# Adquisicion_de_se_al_y_preamplificacion.net
KiCad netlist of a schematic drawn in Altium Designer
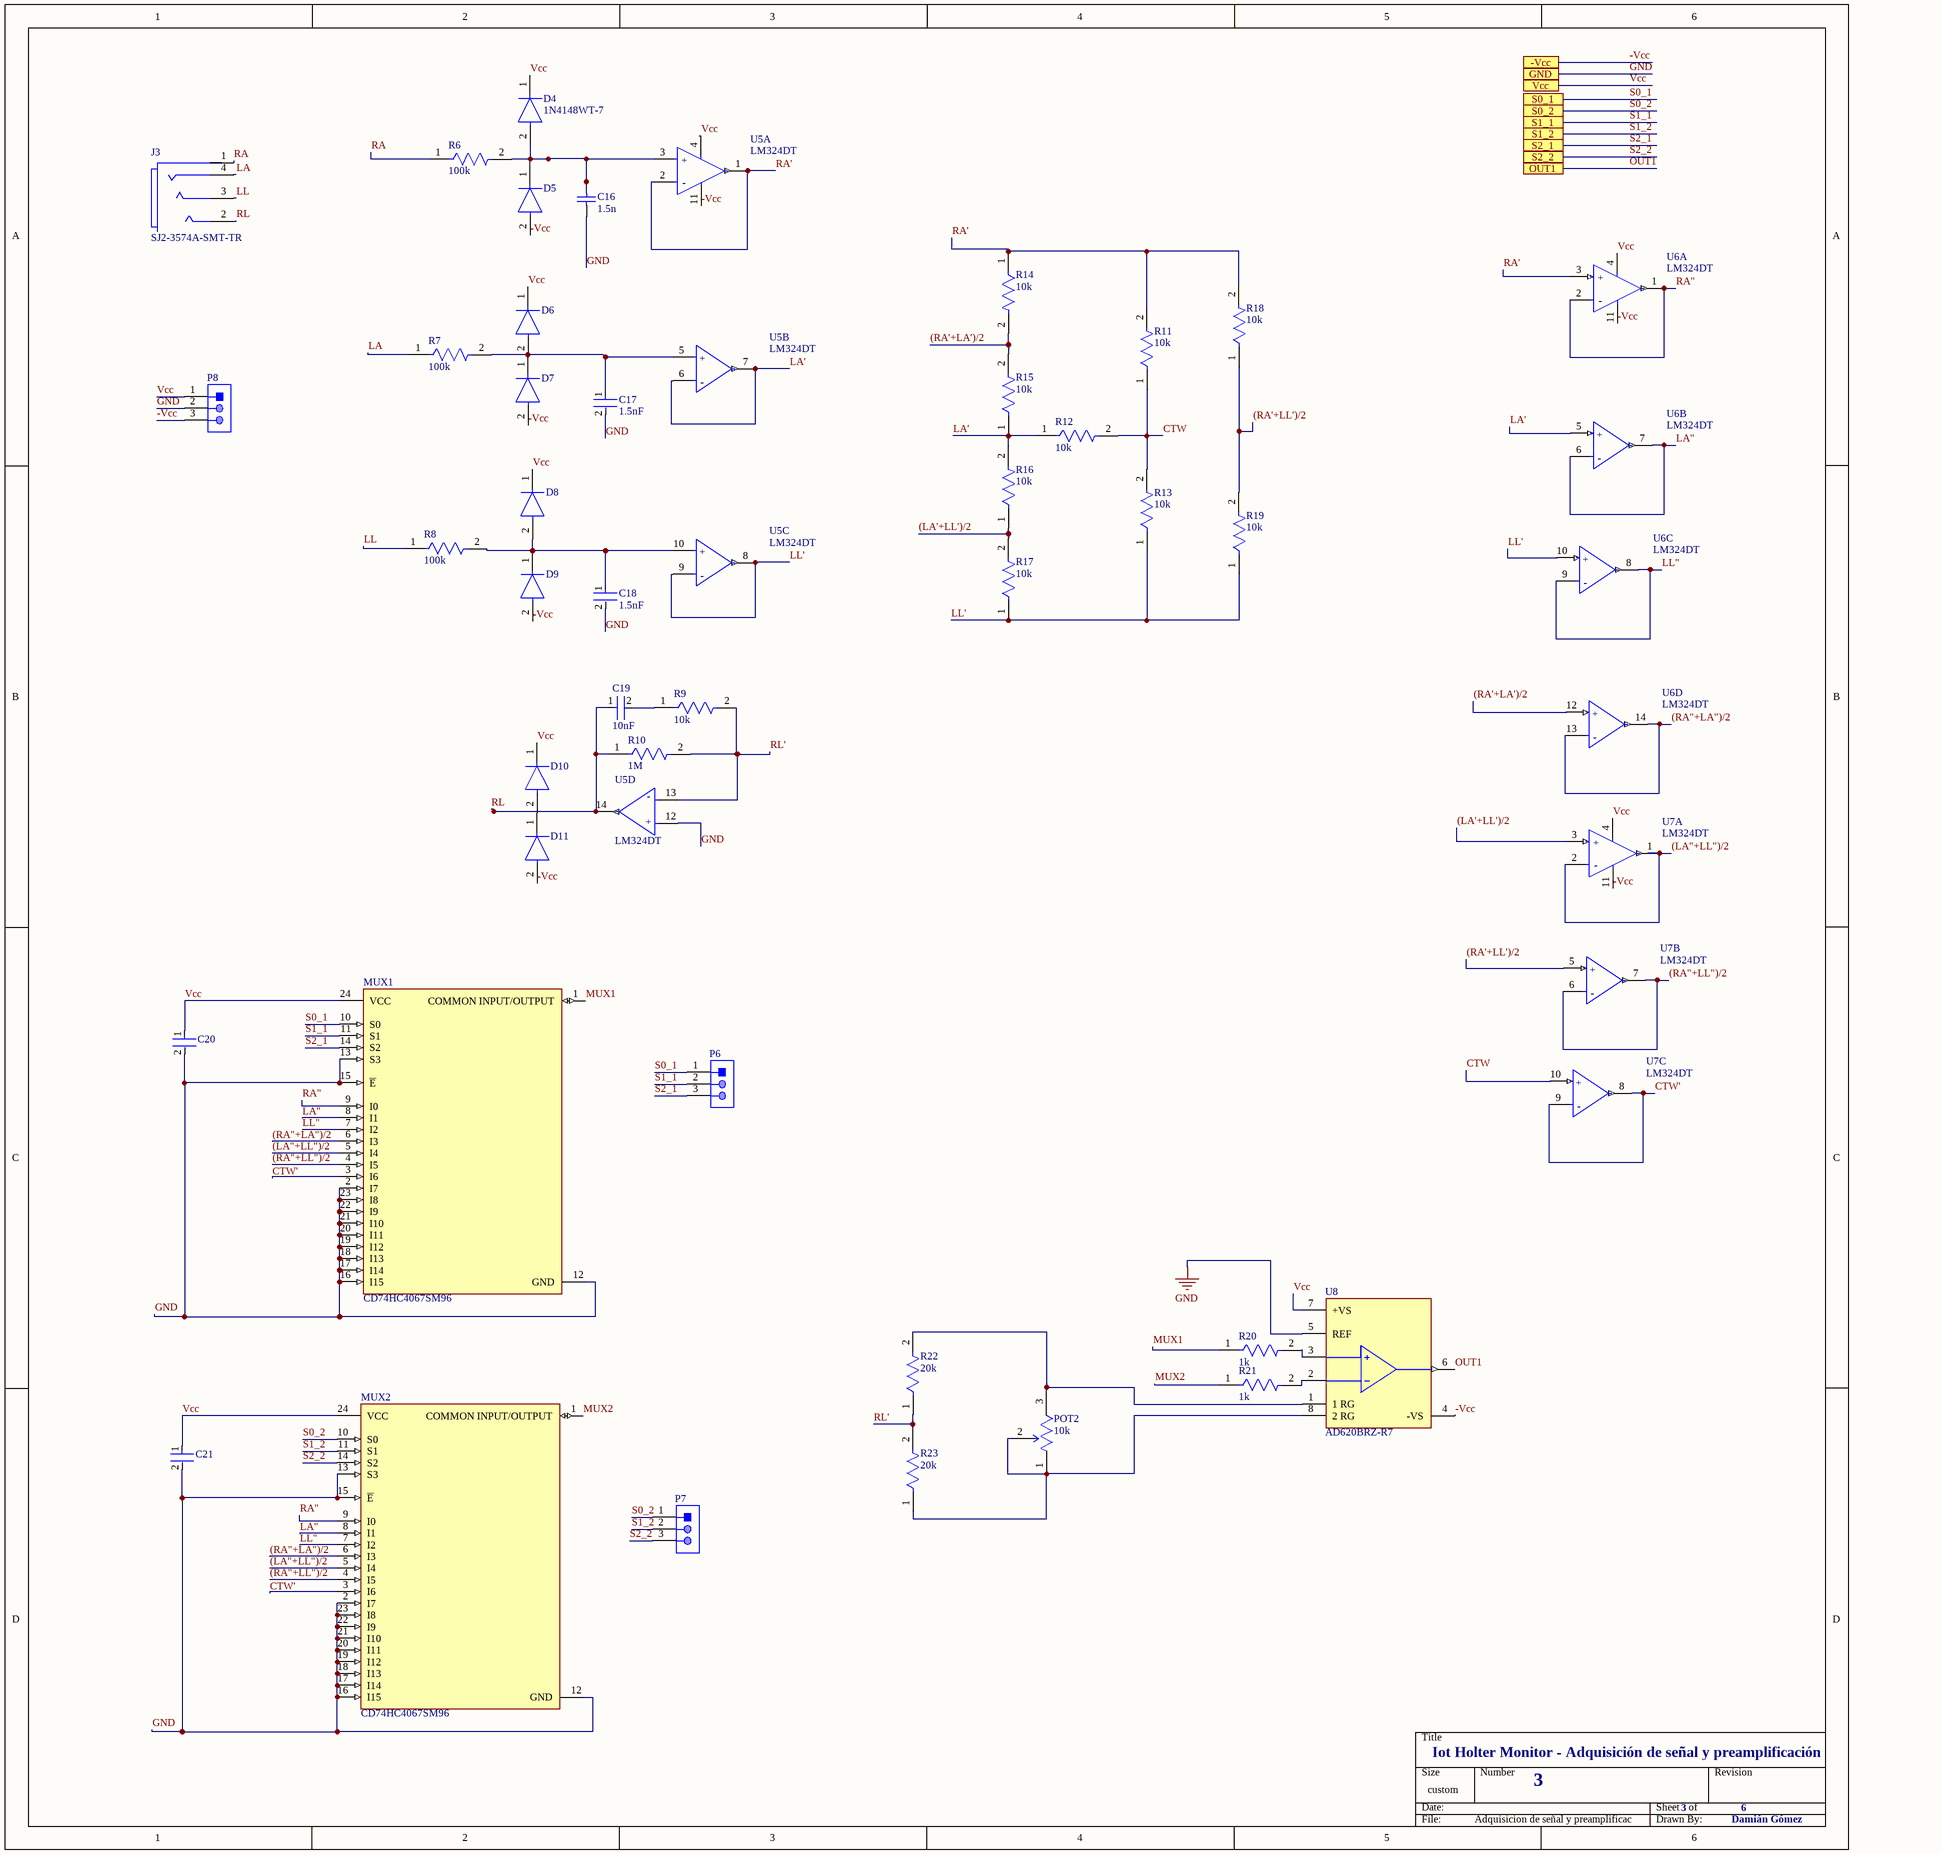
[diagram p0: Adquisicion de señal y preamplificacion.SchDoc]

(export (version "E")
  (design (tool "Eeschema 10.0.6"))
  (components
    (comp (ref "C16")
      (value "1.5n")
      (footprint "KEMT-1206-2_M")
      (description "CAP, Ceramic, 0.1 uF, +/- 10%, 50 V, -55 to 125 degC, 1206 (3216 Metric), RoHS, Tape and Reel")
      (fields (field (name "MANUFACTURER") "Kemet"))
      (libsource (lib "Altium Content Vault") (part "CAP-NP-2"))
    )
    (comp (ref "C17")
      (value "1.5nF")
      (footprint "FP-CL31-IPC_C")
      (description "Cap Ceramic 1.5nF 500V C0G ±5% SMD 1206 +125°C Embossed T/R")
      (fields (field (name "TOLERANCE") "5%"))
      (libsource (lib "Altium Content Vault") (part "b4654b650e69147ec39a6b967a45e02"))
    )
    (comp (ref "C18")
      (value "1.5nF")
      (footprint "FP-CL31-IPC_C")
      (description "Cap Ceramic 1.5nF 500V C0G ±5% SMD 1206 +125°C Embossed T/R")
      (fields (field (name "TOLERANCE") "5%"))
      (libsource (lib "Altium Content Vault") (part "b4654b650e69147ec39a6b967a45e02"))
    )
    (comp (ref "C19")
      (value "10nF")
      (footprint "FP-CL31-IPC_C")
      (description "Cap Ceramic 10nF 500V C0G ±5% SMD 1206 +125°C Embossed T/R")
      (fields (field (name "TOLERANCE") "5%"))
      (libsource (lib "Altium Content Vault") (part "b4654b650e69147ec39a6b967a45e02"))
    )
    (comp (ref "C20")
      (value "~")
      (footprint "FP-0603-L_1_6_0_15-W_0_81-IPC_A")
      (description "General Purpose Ceramic Capacitor, 0603, 1nF, 10%, X7R, 15%, 50V")
      (fields (field (name "VOLTAGE") "50V") (field (name "TOLERANCE") "10%"))
      (libsource (lib "Altium Content Vault") (part "02cd4be3c70576c341d710602a673aa"))
    )
    (comp (ref "C21")
      (value "~")
      (footprint "FP-0603-L_1_6_0_15-W_0_81-IPC_A")
      (description "General Purpose Ceramic Capacitor, 0603, 1nF, 10%, X7R, 15%, 50V")
      (fields (field (name "VOLTAGE") "50V") (field (name "TOLERANCE") "10%"))
      (libsource (lib "Altium Content Vault") (part "02cd4be3c70576c341d710602a673aa"))
    )
    (comp (ref "D4")
      (value "1N4148WT-7")
      (footprint "FP-SOD523-MFG")
      (description "DIODE GEN PURP 80V 125MA SOD523")
      (libsource (lib "Altium Content Vault") (part "d7152d700b627762746794eb795d46e"))
    )
    (comp (ref "D5")
      (value "1N4148WT-7")
      (footprint "FP-SOD523-MFG")
      (description "DIODE GEN PURP 80V 125MA SOD523")
      (libsource (lib "Altium Content Vault") (part "d7152d700b627762746794eb795d46e"))
    )
    (comp (ref "D6")
      (value "1N4148WT-7")
      (footprint "FP-SOD523-MFG")
      (description "DIODE GEN PURP 80V 125MA SOD523")
      (libsource (lib "Altium Content Vault") (part "d7152d700b627762746794eb795d46e"))
    )
    (comp (ref "D7")
      (value "1N4148WT-7")
      (footprint "FP-SOD523-MFG")
      (description "DIODE GEN PURP 80V 125MA SOD523")
      (libsource (lib "Altium Content Vault") (part "d7152d700b627762746794eb795d46e"))
    )
    (comp (ref "D8")
      (value "1N4148WT-7")
      (footprint "FP-SOD523-MFG")
      (description "DIODE GEN PURP 80V 125MA SOD523")
      (libsource (lib "Altium Content Vault") (part "d7152d700b627762746794eb795d46e"))
    )
    (comp (ref "D9")
      (value "1N4148WT-7")
      (footprint "FP-SOD523-MFG")
      (description "DIODE GEN PURP 80V 125MA SOD523")
      (libsource (lib "Altium Content Vault") (part "d7152d700b627762746794eb795d46e"))
    )
    (comp (ref "D10")
      (value "1N4148WT-7")
      (footprint "FP-SOD523-MFG")
      (description "DIODE GEN PURP 80V 125MA SOD523")
      (libsource (lib "Altium Content Vault") (part "d7152d700b627762746794eb795d46e"))
    )
    (comp (ref "D11")
      (value "1N4148WT-7")
      (footprint "FP-SOD523-MFG")
      (description "DIODE GEN PURP 80V 125MA SOD523")
      (libsource (lib "Altium Content Vault") (part "d7152d700b627762746794eb795d46e"))
    )
    (comp (ref "J3")
      (value "SJ2-3574A-SMT-TR")
      (footprint "FP-SJ2-3574A-SMT-TR-MFG")
      (description "AUDIO JACK, 3.5 MM, RT, 4 CONDUC")
      (fields
        (field (name "MANUFACTURER") "CUI")
        (field (name "OCTOPART") "https://octopart.com/sj2-3574a-smt-tr-cui-77838840")
      )
      (libsource (lib "Altium Content Vault") (part "faef30e0bf83b6fb70fb5141942b187"))
    )
    (comp (ref "MUX1")
      (value "CD74HC4067SM96")
      (footprint "FP-DB0024A-IPC_C")
      (description "IC MUX/DEMUX 1X16 24SSOP")
      (libsource (lib "Altium Content Vault") (part "3c03c7c8a240a5fb11098c607706683"))
    )
    (comp (ref "MUX2")
      (value "CD74HC4067SM96")
      (footprint "FP-DB0024A-IPC_C")
      (description "IC MUX/DEMUX 1X16 24SSOP")
      (libsource (lib "Altium Content Vault") (part "3c03c7c8a240a5fb11098c607706683"))
    )
    (comp (ref "P6")
      (value "640456-3")
      (footprint "TECO-640456-3")
      (description "Male Header, Pitch 2.54 mm, 1 x 3 Position, Height 10.03 mm, Tail Length 3.56 mm, -55 to 105 degC")
      (fields (field (name "MANUFACTURER") "TE Connectivity"))
      (libsource (lib "Altium Content Vault") (part "CN-1P-M-R3"))
    )
    (comp (ref "P7")
      (value "640456-3")
      (footprint "TECO-640456-3")
      (description "Male Header, Pitch 2.54 mm, 1 x 3 Position, Height 10.03 mm, Tail Length 3.56 mm, -55 to 105 degC")
      (fields (field (name "MANUFACTURER") "TE Connectivity"))
      (libsource (lib "Altium Content Vault") (part "CN-1P-M-R3"))
    )
    (comp (ref "P8")
      (value "640456-3")
      (footprint "TECO-640456-3")
      (description "Male Header, Pitch 2.54 mm, 1 x 3 Position, Height 10.03 mm, Tail Length 3.56 mm, -55 to 105 degC")
      (fields (field (name "MANUFACTURER") "TE Connectivity"))
      (libsource (lib "Altium Content Vault") (part "CN-1P-M-R3"))
    )
    (comp (ref "POT2")
      (value "10k")
      (footprint "FP-3296W-MFG")
      (description "TRIMMER 10K OHM 0.5W PC PIN TOP")
      (fields (field (name "TOLERANCE") "10%"))
      (libsource (lib "Altium Content Vault") (part "194907ebf2981c0cdd5d9631a0af656"))
    )
    (comp (ref "R6")
      (value "100k")
      (footprint "FP-RC3216-MFG")
      (description "Res Thick Film 1206 1kΩ 5% 0.25W ±100ppm/°C Molded SMD T/R")
      (fields (field (name "TOLERANCE") "5%"))
      (libsource (lib "Altium Content Vault") (part "1029c3af85768c4190bb7ad29bc67b5"))
    )
    (comp (ref "R7")
      (value "100k")
      (footprint "FP-RC3216-MFG")
      (description "Res Thick Film 1206 1kΩ 5% 0.25W ±100ppm/°C Molded SMD T/R")
      (fields (field (name "TOLERANCE") "5%"))
      (libsource (lib "Altium Content Vault") (part "1029c3af85768c4190bb7ad29bc67b5"))
    )
    (comp (ref "R8")
      (value "100k")
      (footprint "FP-RC3216-MFG")
      (description "Res Thick Film 1206 1kΩ 5% 0.25W ±100ppm/°C Molded SMD T/R")
      (fields (field (name "TOLERANCE") "5%"))
      (libsource (lib "Altium Content Vault") (part "1029c3af85768c4190bb7ad29bc67b5"))
    )
    (comp (ref "R9")
      (value "10k")
      (footprint "FP-RC3216-MFG")
      (description "Res Thick Film 1206 10kΩ 5% 0.25W ±100ppm/°C Molded SMD T/R")
      (fields (field (name "TOLERANCE") "5%"))
      (libsource (lib "Altium Content Vault") (part "1029c3af85768c4190bb7ad29bc67b5"))
    )
    (comp (ref "R10")
      (value "1M")
      (footprint "FP-RC3216-MFG")
      (description "Res Thick Film 1206 1MΩ 5% 0.25W ±100ppm/°C Molded SMD T/R")
      (fields (field (name "TOLERANCE") "5%"))
      (libsource (lib "Altium Content Vault") (part "1029c3af85768c4190bb7ad29bc67b5"))
    )
    (comp (ref "R11")
      (value "10k")
      (footprint "FP-RC3216-MFG")
      (description "Res Thick Film 1206 10kΩ 5% 0.25W ±100ppm/°C Molded SMD T/R")
      (fields (field (name "TOLERANCE") "5%"))
      (libsource (lib "Altium Content Vault") (part "1029c3af85768c4190bb7ad29bc67b5"))
    )
    (comp (ref "R12")
      (value "10k")
      (footprint "FP-RC3216-MFG")
      (description "Res Thick Film 1206 10kΩ 5% 0.25W ±100ppm/°C Molded SMD T/R")
      (fields (field (name "TOLERANCE") "5%"))
      (libsource (lib "Altium Content Vault") (part "1029c3af85768c4190bb7ad29bc67b5"))
    )
    (comp (ref "R13")
      (value "10k")
      (footprint "FP-RC3216-MFG")
      (description "Res Thick Film 1206 10kΩ 5% 0.25W ±100ppm/°C Molded SMD T/R")
      (fields (field (name "TOLERANCE") "5%"))
      (libsource (lib "Altium Content Vault") (part "1029c3af85768c4190bb7ad29bc67b5"))
    )
    (comp (ref "R14")
      (value "10k")
      (footprint "FP-RC3216-MFG")
      (description "Res Thick Film 1206 10kΩ 5% 0.25W ±100ppm/°C Molded SMD T/R")
      (fields (field (name "TOLERANCE") "5%"))
      (libsource (lib "Altium Content Vault") (part "1029c3af85768c4190bb7ad29bc67b5"))
    )
    (comp (ref "R15")
      (value "10k")
      (footprint "FP-RC3216-MFG")
      (description "Res Thick Film 1206 10kΩ 5% 0.25W ±100ppm/°C Molded SMD T/R")
      (fields (field (name "TOLERANCE") "5%"))
      (libsource (lib "Altium Content Vault") (part "1029c3af85768c4190bb7ad29bc67b5"))
    )
    (comp (ref "R16")
      (value "10k")
      (footprint "FP-RC3216-MFG")
      (description "Res Thick Film 1206 10kΩ 5% 0.25W ±100ppm/°C Molded SMD T/R")
      (fields (field (name "TOLERANCE") "5%"))
      (libsource (lib "Altium Content Vault") (part "1029c3af85768c4190bb7ad29bc67b5"))
    )
    (comp (ref "R17")
      (value "10k")
      (footprint "FP-RC3216-MFG")
      (description "Res Thick Film 1206 10kΩ 5% 0.25W ±100ppm/°C Molded SMD T/R")
      (fields (field (name "TOLERANCE") "5%"))
      (libsource (lib "Altium Content Vault") (part "1029c3af85768c4190bb7ad29bc67b5"))
    )
    (comp (ref "R18")
      (value "10k")
      (footprint "FP-RC3216-MFG")
      (description "Res Thick Film 1206 10kΩ 5% 0.25W ±100ppm/°C Molded SMD T/R")
      (fields (field (name "TOLERANCE") "5%"))
      (libsource (lib "Altium Content Vault") (part "1029c3af85768c4190bb7ad29bc67b5"))
    )
    (comp (ref "R19")
      (value "10k")
      (footprint "FP-RC3216-MFG")
      (description "Res Thick Film 1206 10kΩ 5% 0.25W ±100ppm/°C Molded SMD T/R")
      (fields (field (name "TOLERANCE") "5%"))
      (libsource (lib "Altium Content Vault") (part "1029c3af85768c4190bb7ad29bc67b5"))
    )
    (comp (ref "R20")
      (value "1k")
      (footprint "FP-RC3216-MFG")
      (description "Res Thick Film 1206 1kΩ 5% 0.25W ±100ppm/°C Molded SMD T/R")
      (fields (field (name "TOLERANCE") "5%"))
      (libsource (lib "Altium Content Vault") (part "1029c3af85768c4190bb7ad29bc67b5"))
    )
    (comp (ref "R21")
      (value "1k")
      (footprint "FP-RC3216-MFG")
      (description "Res Thick Film 1206 1kΩ 5% 0.25W ±100ppm/°C Molded SMD T/R")
      (fields (field (name "TOLERANCE") "5%"))
      (libsource (lib "Altium Content Vault") (part "1029c3af85768c4190bb7ad29bc67b5"))
    )
    (comp (ref "R22")
      (value "20k")
      (footprint "FP-RC3216-MFG")
      (description "Res Thick Film 1206 20kΩ 5% 0.25W ±100ppm/°C Molded SMD T/R")
      (fields (field (name "TOLERANCE") "5%"))
      (libsource (lib "Altium Content Vault") (part "1029c3af85768c4190bb7ad29bc67b5"))
    )
    (comp (ref "R23")
      (value "20k")
      (footprint "FP-RC3216-MFG")
      (description "Res Thick Film 1206 20kΩ 5% 0.25W ±100ppm/°C Molded SMD T/R")
      (fields (field (name "TOLERANCE") "5%"))
      (libsource (lib "Altium Content Vault") (part "1029c3af85768c4190bb7ad29bc67b5"))
    )
    (comp (ref "U5")
      (value "LM324DT")
      (footprint "FP-SO-14-MFG")
      (description "IC OPAMP GP 4 CIRCUIT 14SO")
      (fields
        (field (name "OCTOPART") "https://octopart.com/lm324dt-stmicroelectronics-39579146")
        (field (name "MANUFACTURER") "STMicroelectronics")
      )
      (libsource (lib "Altium Content Vault") (part "a065ef67e5aa9ef3942d43d6008d043"))
    )
    (comp (ref "U6")
      (value "LM324DT")
      (footprint "FP-SO-14-MFG")
      (description "IC OPAMP GP 4 CIRCUIT 14SO")
      (fields
        (field (name "OCTOPART") "https://octopart.com/lm324dt-stmicroelectronics-39579146")
        (field (name "MANUFACTURER") "STMicroelectronics")
      )
      (libsource (lib "Altium Content Vault") (part "a065ef67e5aa9ef3942d43d6008d043"))
    )
    (comp (ref "U7")
      (value "LM324DT")
      (footprint "FP-SO-14-MFG")
      (description "IC OPAMP GP 4 CIRCUIT 14SO")
      (fields
        (field (name "OCTOPART") "https://octopart.com/lm324dt-stmicroelectronics-39579146")
        (field (name "MANUFACTURER") "STMicroelectronics")
      )
      (libsource (lib "Altium Content Vault") (part "a065ef67e5aa9ef3942d43d6008d043"))
    )
    (comp (ref "U8")
      (value "AD620BRZ-R7")
      (footprint "FP-R-8-IPC_C")
      (description "IC INST AMP 1 CIRCUIT 8SOIC")
      (libsource (lib "Altium Content Vault") (part "34122d4f8c853147fd0c9ba0f33876e"))
    )
  )
  (nets
    (net (code "1") (name "/(LA\"+LL\"){slash}2") (class "Default")
      (node (ref "MUX1") (pin "5") (pinfunction "I4_5") (pintype "input"))
      (node (ref "MUX2") (pin "5") (pinfunction "I4_5") (pintype "input"))
      (node (ref "U7") (pin "1") (pinfunction "Output_1_1") (pintype "output"))
      (node (ref "U7") (pin "2") (pinfunction "Inverting_Input_1_2") (pintype "passive"))
    )
    (net (code "2") (name "/(LA'+LL'){slash}2") (class "Default")
      (node (ref "R16") (pin "1") (pinfunction "1_1") (pintype "passive"))
      (node (ref "R17") (pin "2") (pinfunction "2_2") (pintype "passive"))
      (node (ref "U7") (pin "3") (pinfunction "Non-Inverting_Input_1_3") (pintype "tri_state"))
    )
    (net (code "3") (name "/(RA\"+LA\"){slash}2") (class "Default")
      (node (ref "MUX1") (pin "6") (pinfunction "I3_6") (pintype "input"))
      (node (ref "MUX2") (pin "6") (pinfunction "I3_6") (pintype "input"))
      (node (ref "U6") (pin "13") (pinfunction "Inverting_Input_4_13") (pintype "tri_state"))
      (node (ref "U6") (pin "14") (pinfunction "Output_4_14") (pintype "output"))
    )
    (net (code "4") (name "/(RA\"+LL\"){slash}2") (class "Default")
      (node (ref "MUX1") (pin "4") (pinfunction "I5_4") (pintype "input"))
      (node (ref "MUX2") (pin "4") (pinfunction "I5_4") (pintype "input"))
      (node (ref "U7") (pin "6") (pinfunction "Inverting_Input_2_6") (pintype "tri_state"))
      (node (ref "U7") (pin "7") (pinfunction "Output_2_7") (pintype "output"))
    )
    (net (code "5") (name "/(RA'+LA'){slash}2") (class "Default")
      (node (ref "R14") (pin "2") (pinfunction "2_2") (pintype "passive"))
      (node (ref "R15") (pin "2") (pinfunction "2_2") (pintype "passive"))
      (node (ref "U6") (pin "12") (pinfunction "Non-Inverting_Input_4_12") (pintype "tri_state"))
    )
    (net (code "6") (name "/(RA'+LL'){slash}2") (class "Default")
      (node (ref "R18") (pin "1") (pinfunction "1_1") (pintype "passive"))
      (node (ref "R19") (pin "2") (pinfunction "2_2") (pintype "passive"))
      (node (ref "U7") (pin "5") (pinfunction "Non-Inverting_Input_2_5") (pintype "tri_state"))
    )
    (net (code "7") (name "/-Vcc") (class "Default")
      (node (ref "D11") (pin "2") (pinfunction "A_2") (pintype "passive"))
      (node (ref "D5") (pin "2") (pinfunction "A_2") (pintype "passive"))
      (node (ref "D7") (pin "2") (pinfunction "A_2") (pintype "passive"))
      (node (ref "D9") (pin "2") (pinfunction "A_2") (pintype "passive"))
      (node (ref "P8") (pin "3") (pinfunction "3_3") (pintype "passive"))
      (node (ref "U5") (pin "11") (pinfunction "VCC-_11") (pintype "power_in"))
      (node (ref "U6") (pin "11") (pinfunction "VCC-_11") (pintype "power_in"))
      (node (ref "U7") (pin "11") (pinfunction "VCC-_11") (pintype "power_in"))
      (node (ref "U8") (pin "4") (pinfunction "-VS_4") (pintype "power_in"))
    )
    (net (code "8") (name "/CTW") (class "Default")
      (node (ref "R11") (pin "1") (pinfunction "1_1") (pintype "passive"))
      (node (ref "R12") (pin "2") (pinfunction "2_2") (pintype "passive"))
      (node (ref "R13") (pin "2") (pinfunction "2_2") (pintype "passive"))
      (node (ref "U7") (pin "10") (pinfunction "Non-Inverting_Input_3_10") (pintype "tri_state"))
    )
    (net (code "9") (name "/CTW'") (class "Default")
      (node (ref "MUX1") (pin "3") (pinfunction "I6_3") (pintype "input"))
      (node (ref "MUX2") (pin "3") (pinfunction "I6_3") (pintype "input"))
      (node (ref "U7") (pin "8") (pinfunction "Output_3_8") (pintype "output"))
      (node (ref "U7") (pin "9") (pinfunction "Inverting_Input_3_9") (pintype "tri_state"))
    )
    (net (code "10") (name "/LA") (class "Default")
      (node (ref "J3") (pin "4") (pinfunction "ring_2_4") (pintype "passive"))
      (node (ref "R7") (pin "1") (pinfunction "1_1") (pintype "passive"))
    )
    (net (code "11") (name "/LA\"") (class "Default")
      (node (ref "MUX1") (pin "8") (pinfunction "I1_8") (pintype "input"))
      (node (ref "MUX2") (pin "8") (pinfunction "I1_8") (pintype "input"))
      (node (ref "U6") (pin "6") (pinfunction "Inverting_Input_2_6") (pintype "tri_state"))
      (node (ref "U6") (pin "7") (pinfunction "Output_2_7") (pintype "output"))
    )
    (net (code "12") (name "/LA'") (class "Default")
      (node (ref "R12") (pin "1") (pinfunction "1_1") (pintype "passive"))
      (node (ref "R15") (pin "1") (pinfunction "1_1") (pintype "passive"))
      (node (ref "R16") (pin "2") (pinfunction "2_2") (pintype "passive"))
      (node (ref "U5") (pin "6") (pinfunction "Inverting_Input_2_6") (pintype "tri_state"))
      (node (ref "U5") (pin "7") (pinfunction "Output_2_7") (pintype "output"))
      (node (ref "U6") (pin "5") (pinfunction "Non-Inverting_Input_2_5") (pintype "tri_state"))
    )
    (net (code "13") (name "/LL") (class "Default")
      (node (ref "J3") (pin "3") (pinfunction "ring_1_3") (pintype "passive"))
      (node (ref "R8") (pin "1") (pinfunction "1_1") (pintype "passive"))
    )
    (net (code "14") (name "/LL\"") (class "Default")
      (node (ref "MUX1") (pin "7") (pinfunction "I2_7") (pintype "input"))
      (node (ref "MUX2") (pin "7") (pinfunction "I2_7") (pintype "input"))
      (node (ref "U6") (pin "8") (pinfunction "Output_3_8") (pintype "output"))
      (node (ref "U6") (pin "9") (pinfunction "Inverting_Input_3_9") (pintype "tri_state"))
    )
    (net (code "15") (name "/LL'") (class "Default")
      (node (ref "R13") (pin "1") (pinfunction "1_1") (pintype "passive"))
      (node (ref "R17") (pin "1") (pinfunction "1_1") (pintype "passive"))
      (node (ref "R19") (pin "1") (pinfunction "1_1") (pintype "passive"))
      (node (ref "U5") (pin "8") (pinfunction "Output_3_8") (pintype "output"))
      (node (ref "U5") (pin "9") (pinfunction "Inverting_Input_3_9") (pintype "tri_state"))
      (node (ref "U6") (pin "10") (pinfunction "Non-Inverting_Input_3_10") (pintype "tri_state"))
    )
    (net (code "16") (name "/MUX1") (class "Default")
      (node (ref "MUX1") (pin "1") (pinfunction "COMMON_INPUT/OUTPUT_1") (pintype "bidirectional"))
      (node (ref "R20") (pin "1") (pinfunction "1_1") (pintype "passive"))
    )
    (net (code "17") (name "/MUX2") (class "Default")
      (node (ref "MUX2") (pin "1") (pinfunction "COMMON_INPUT/OUTPUT_1") (pintype "bidirectional"))
      (node (ref "R21") (pin "1") (pinfunction "1_1") (pintype "passive"))
    )
    (net (code "18") (name "/OUT1") (class "Default")
      (node (ref "U8") (pin "6") (pinfunction "OUTPUT_6") (pintype "output"))
    )
    (net (code "19") (name "/RA") (class "Default")
      (node (ref "J3") (pin "1") (pinfunction "sleeve_1") (pintype "passive"))
      (node (ref "R6") (pin "1") (pinfunction "1_1") (pintype "passive"))
    )
    (net (code "20") (name "/RA\"") (class "Default")
      (node (ref "MUX1") (pin "9") (pinfunction "I0_9") (pintype "input"))
      (node (ref "MUX2") (pin "9") (pinfunction "I0_9") (pintype "input"))
      (node (ref "U6") (pin "1") (pinfunction "Output_1_1") (pintype "output"))
      (node (ref "U6") (pin "2") (pinfunction "Inverting_Input_1_2") (pintype "passive"))
    )
    (net (code "21") (name "/RA'") (class "Default")
      (node (ref "R11") (pin "2") (pinfunction "2_2") (pintype "passive"))
      (node (ref "R14") (pin "1") (pinfunction "1_1") (pintype "passive"))
      (node (ref "R18") (pin "2") (pinfunction "2_2") (pintype "passive"))
      (node (ref "U5") (pin "1") (pinfunction "Output_1_1") (pintype "output"))
      (node (ref "U5") (pin "2") (pinfunction "Inverting_Input_1_2") (pintype "passive"))
      (node (ref "U6") (pin "3") (pinfunction "Non-Inverting_Input_1_3") (pintype "tri_state"))
    )
    (net (code "22") (name "/RL") (class "Default")
      (node (ref "C19") (pin "1") (pinfunction "1_1") (pintype "passive"))
      (node (ref "J3") (pin "2") (pinfunction "tip_2") (pintype "passive"))
      (node (ref "R10") (pin "1") (pinfunction "1_1") (pintype "passive"))
      (node (ref "U5") (pin "14") (pinfunction "Output_4_14") (pintype "output"))
    )
    (net (code "23") (name "/RL'") (class "Default")
      (node (ref "R10") (pin "2") (pinfunction "2_2") (pintype "passive"))
      (node (ref "R22") (pin "1") (pinfunction "1_1") (pintype "passive"))
      (node (ref "R23") (pin "2") (pinfunction "2_2") (pintype "passive"))
      (node (ref "R9") (pin "2") (pinfunction "2_2") (pintype "passive"))
      (node (ref "U5") (pin "13") (pinfunction "Inverting_Input_4_13") (pintype "tri_state"))
    )
    (net (code "24") (name "/S0_1") (class "Default")
      (node (ref "MUX1") (pin "10") (pinfunction "S0_10") (pintype "input"))
      (node (ref "P6") (pin "1") (pinfunction "1_1") (pintype "passive"))
    )
    (net (code "25") (name "/S0_2") (class "Default")
      (node (ref "MUX2") (pin "10") (pinfunction "S0_10") (pintype "input"))
      (node (ref "P7") (pin "1") (pinfunction "1_1") (pintype "passive"))
    )
    (net (code "26") (name "/S1_1") (class "Default")
      (node (ref "MUX1") (pin "11") (pinfunction "S1_11") (pintype "input"))
      (node (ref "P6") (pin "2") (pinfunction "2_2") (pintype "passive"))
    )
    (net (code "27") (name "/S1_2") (class "Default")
      (node (ref "MUX2") (pin "11") (pinfunction "S1_11") (pintype "input"))
      (node (ref "P7") (pin "2") (pinfunction "2_2") (pintype "passive"))
    )
    (net (code "28") (name "/S2_1") (class "Default")
      (node (ref "MUX1") (pin "14") (pinfunction "S2_14") (pintype "input"))
      (node (ref "P6") (pin "3") (pinfunction "3_3") (pintype "passive"))
    )
    (net (code "29") (name "/S2_2") (class "Default")
      (node (ref "MUX2") (pin "14") (pinfunction "S2_14") (pintype "input"))
      (node (ref "P7") (pin "3") (pinfunction "3_3") (pintype "passive"))
    )
    (net (code "30") (name "/Vcc") (class "Default")
      (node (ref "C20") (pin "1") (pinfunction "1_1") (pintype "passive"))
      (node (ref "C21") (pin "1") (pinfunction "1_1") (pintype "passive"))
      (node (ref "D10") (pin "1") (pinfunction "C_1") (pintype "passive"))
      (node (ref "D4") (pin "1") (pinfunction "C_1") (pintype "passive"))
      (node (ref "D6") (pin "1") (pinfunction "C_1") (pintype "passive"))
      (node (ref "D8") (pin "1") (pinfunction "C_1") (pintype "passive"))
      (node (ref "MUX1") (pin "24") (pinfunction "VCC_24") (pintype "power_in"))
      (node (ref "MUX2") (pin "24") (pinfunction "VCC_24") (pintype "power_in"))
      (node (ref "P8") (pin "1") (pinfunction "1_1") (pintype "passive"))
      (node (ref "U5") (pin "4") (pinfunction "VCC+_4") (pintype "power_in"))
      (node (ref "U6") (pin "4") (pinfunction "VCC+_4") (pintype "power_in"))
      (node (ref "U7") (pin "4") (pinfunction "VCC+_4") (pintype "power_in"))
      (node (ref "U8") (pin "7") (pinfunction "+VS_7") (pintype "power_in"))
    )
    (net (code "31") (name "GND") (class "Default")
      (node (ref "C16") (pin "1") (pinfunction "1_1") (pintype "passive"))
      (node (ref "C17") (pin "2") (pinfunction "2_2") (pintype "passive"))
      (node (ref "C18") (pin "2") (pinfunction "2_2") (pintype "passive"))
      (node (ref "C20") (pin "2") (pinfunction "2_2") (pintype "passive"))
      (node (ref "C21") (pin "2") (pinfunction "2_2") (pintype "passive"))
      (node (ref "MUX1") (pin "12") (pinfunction "GND_12") (pintype "passive"))
      (node (ref "MUX1") (pin "13") (pinfunction "S3_13") (pintype "input"))
      (node (ref "MUX1") (pin "15") (pinfunction "~{E}_15") (pintype "input"))
      (node (ref "MUX1") (pin "16") (pinfunction "I15_16") (pintype "input"))
      (node (ref "MUX1") (pin "17") (pinfunction "I14_17") (pintype "input"))
      (node (ref "MUX1") (pin "18") (pinfunction "I13_18") (pintype "input"))
      (node (ref "MUX1") (pin "19") (pinfunction "I12_19") (pintype "input"))
      (node (ref "MUX1") (pin "2") (pinfunction "I7_2") (pintype "input"))
      (node (ref "MUX1") (pin "20") (pinfunction "I11_20") (pintype "input"))
      (node (ref "MUX1") (pin "21") (pinfunction "I10_21") (pintype "input"))
      (node (ref "MUX1") (pin "22") (pinfunction "I9_22") (pintype "input"))
      (node (ref "MUX1") (pin "23") (pinfunction "I8_23") (pintype "input"))
      (node (ref "MUX2") (pin "12") (pinfunction "GND_12") (pintype "passive"))
      (node (ref "MUX2") (pin "13") (pinfunction "S3_13") (pintype "input"))
      (node (ref "MUX2") (pin "15") (pinfunction "~{E}_15") (pintype "input"))
      (node (ref "MUX2") (pin "16") (pinfunction "I15_16") (pintype "input"))
      (node (ref "MUX2") (pin "17") (pinfunction "I14_17") (pintype "input"))
      (node (ref "MUX2") (pin "18") (pinfunction "I13_18") (pintype "input"))
      (node (ref "MUX2") (pin "19") (pinfunction "I12_19") (pintype "input"))
      (node (ref "MUX2") (pin "2") (pinfunction "I7_2") (pintype "input"))
      (node (ref "MUX2") (pin "20") (pinfunction "I11_20") (pintype "input"))
      (node (ref "MUX2") (pin "21") (pinfunction "I10_21") (pintype "input"))
      (node (ref "MUX2") (pin "22") (pinfunction "I9_22") (pintype "input"))
      (node (ref "MUX2") (pin "23") (pinfunction "I8_23") (pintype "input"))
      (node (ref "P8") (pin "2") (pinfunction "2_2") (pintype "passive"))
      (node (ref "U5") (pin "12") (pinfunction "Non-Inverting_Input_4_12") (pintype "tri_state"))
      (node (ref "U8") (pin "5") (pinfunction "REF_5") (pintype "passive"))
    )
    (net (code "32") (name "Net-(C19-Pad2)") (class "Default")
      (node (ref "C19") (pin "2") (pinfunction "2_2") (pintype "passive"))
      (node (ref "R9") (pin "1") (pinfunction "1_1") (pintype "passive"))
    )
    (net (code "33") (name "Net-(D4-A)") (class "Default")
      (node (ref "C16") (pin "2") (pinfunction "2_2") (pintype "passive"))
      (node (ref "D4") (pin "2") (pinfunction "A_2") (pintype "passive"))
      (node (ref "D5") (pin "1") (pinfunction "C_1") (pintype "passive"))
      (node (ref "R6") (pin "2") (pinfunction "2_2") (pintype "passive"))
      (node (ref "U5") (pin "3") (pinfunction "Non-Inverting_Input_1_3") (pintype "tri_state"))
    )
    (net (code "34") (name "Net-(D6-A)") (class "Default")
      (node (ref "C17") (pin "1") (pinfunction "1_1") (pintype "passive"))
      (node (ref "D6") (pin "2") (pinfunction "A_2") (pintype "passive"))
      (node (ref "D7") (pin "1") (pinfunction "C_1") (pintype "passive"))
      (node (ref "R7") (pin "2") (pinfunction "2_2") (pintype "passive"))
      (node (ref "U5") (pin "5") (pinfunction "Non-Inverting_Input_2_5") (pintype "tri_state"))
    )
    (net (code "35") (name "Net-(D8-A)") (class "Default")
      (node (ref "C18") (pin "1") (pinfunction "1_1") (pintype "passive"))
      (node (ref "D8") (pin "2") (pinfunction "A_2") (pintype "passive"))
      (node (ref "D9") (pin "1") (pinfunction "C_1") (pintype "passive"))
      (node (ref "R8") (pin "2") (pinfunction "2_2") (pintype "passive"))
      (node (ref "U5") (pin "10") (pinfunction "Non-Inverting_Input_3_10") (pintype "tri_state"))
    )
    (net (code "36") (name "Net-(D10-A)") (class "Default")
      (node (ref "D10") (pin "2") (pinfunction "A_2") (pintype "passive"))
      (node (ref "D11") (pin "1") (pinfunction "C_1") (pintype "passive"))
    )
    (net (code "37") (name "Net-(POT2-CCW)") (class "Default")
      (node (ref "POT2") (pin "1") (pinfunction "CCW_1") (pintype "passive"))
      (node (ref "POT2") (pin "2") (pinfunction "WIPER_2") (pintype "passive"))
      (node (ref "R23") (pin "1") (pinfunction "1_1") (pintype "passive"))
      (node (ref "U8") (pin "8") (pinfunction "2_RG_8") (pintype "passive"))
    )
    (net (code "38") (name "Net-(POT2-CW)") (class "Default")
      (node (ref "POT2") (pin "3") (pinfunction "CW_3") (pintype "passive"))
      (node (ref "R22") (pin "2") (pinfunction "2_2") (pintype "passive"))
      (node (ref "U8") (pin "1") (pinfunction "1_RG_1") (pintype "passive"))
    )
    (net (code "39") (name "Net-(U8-+IN)") (class "Default")
      (node (ref "R20") (pin "2") (pinfunction "2_2") (pintype "passive"))
      (node (ref "U8") (pin "3") (pinfunction "+IN_3") (pintype "tri_state"))
    )
    (net (code "40") (name "Net-(U8--IN)") (class "Default")
      (node (ref "R21") (pin "2") (pinfunction "2_2") (pintype "passive"))
      (node (ref "U8") (pin "2") (pinfunction "-IN_2") (pintype "tri_state"))
    )
  )
)
